# Conn.net
KiCad netlist of a schematic drawn in Altium Designer
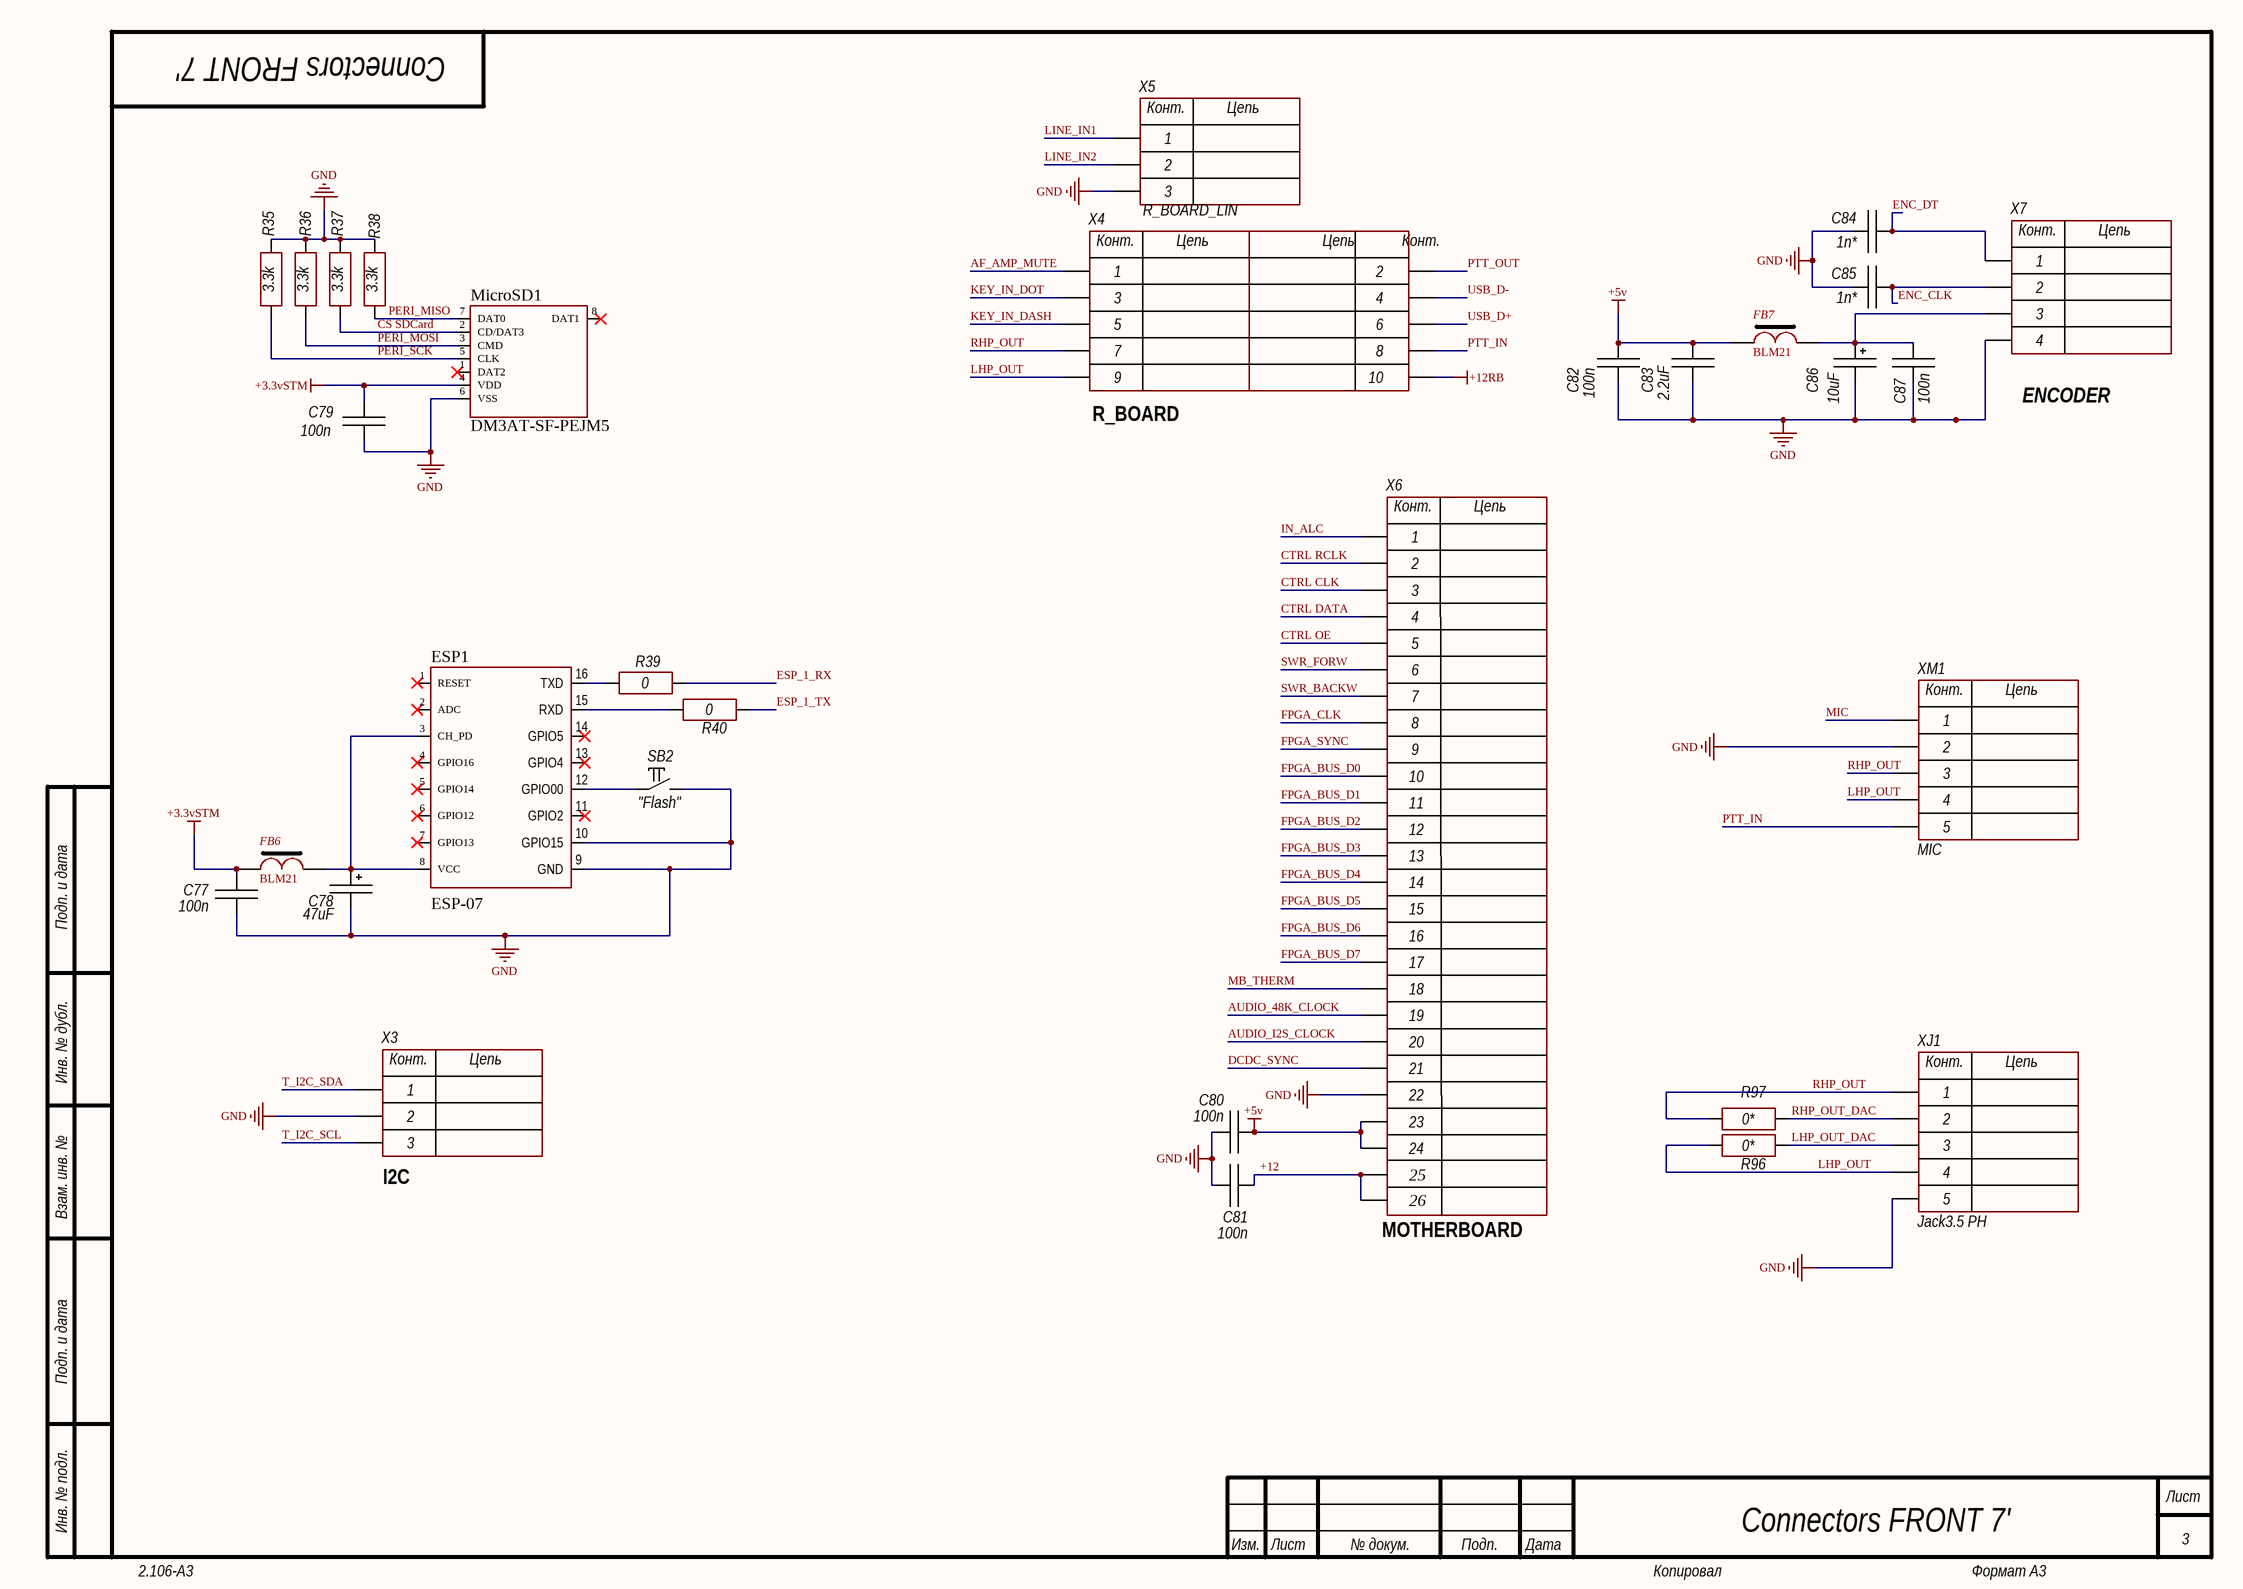
[diagram p0: Conn.SchDoc]

(export (version "E")
  (design (tool "Eeschema 10.0.6"))
  (components
    (comp (ref "C77")
      (value "100n")
      (footprint "standard:CH0805C")
      (libsource (lib "Discrete") (part "Capacitor"))
    )
    (comp (ref "C78")
      (value "47uF")
      (footprint "standard:TANTAL_C")
      (libsource (lib "Discrete") (part "TantalCap"))
    )
    (comp (ref "C79")
      (value "100n")
      (footprint "standard:CH0805C")
      (libsource (lib "Discrete") (part "Capacitor"))
    )
    (comp (ref "C80")
      (value "100n")
      (footprint "standard:CH0805C")
      (libsource (lib "Discrete") (part "Capacitor"))
    )
    (comp (ref "C81")
      (value "100n")
      (footprint "standard:CH0805C")
      (libsource (lib "Discrete") (part "Capacitor"))
    )
    (comp (ref "C82")
      (value "100n")
      (footprint "standard:CH0805C")
      (libsource (lib "Discrete") (part "Capacitor"))
    )
    (comp (ref "C83")
      (value "2.2uF")
      (footprint "standard:CH0805C")
      (libsource (lib "Discrete") (part "Capacitor"))
    )
    (comp (ref "C84")
      (value "1n*")
      (footprint "standard:CH0805C")
      (libsource (lib "Discrete") (part "Capacitor"))
    )
    (comp (ref "C85")
      (value "1n*")
      (footprint "standard:CH0805C")
      (libsource (lib "Discrete") (part "Capacitor"))
    )
    (comp (ref "C86")
      (value "10uF")
      (footprint "standard:TANTAL_B")
      (libsource (lib "Discrete") (part "TantalCap"))
    )
    (comp (ref "C87")
      (value "100n")
      (footprint "standard:CH0805C")
      (libsource (lib "Discrete") (part "Capacitor"))
    )
    (comp (ref "ESP1")
      (value "ESP-07")
      (footprint "ESP8266 ESP-07")
      (libsource (lib "Discrete") (part "ESP-07"))
    )
    (comp (ref "FB6") (value "BLM21") (footprint "CH0805L") (libsource (lib "Discrete") (part "FB-1")))
    (comp (ref "FB7") (value "BLM21") (footprint "CH0805L") (libsource (lib "Discrete") (part "FB-1")))
    (comp (ref "MicroSD1")
      (value "DM3AT-SF-PEJM5")
      (footprint "SD-card")
      (libsource (lib "Discrete") (part "MicroSD"))
    )
    (comp (ref "R35") (value "3.3k") (footprint "standard:CH0805R") (libsource (lib "") (part "Resistor_1")))
    (comp (ref "R36") (value "3.3k") (footprint "standard:CH0805R") (libsource (lib "") (part "Resistor_1")))
    (comp (ref "R37") (value "3.3k") (footprint "standard:CH0805R") (libsource (lib "") (part "Resistor_1")))
    (comp (ref "R38") (value "3.3k") (footprint "standard:CH0805R") (libsource (lib "") (part "Resistor_1")))
    (comp (ref "R39")
      (value "0")
      (footprint "standard:CH0603R")
      (libsource (lib "Discrete") (part "Resistor"))
    )
    (comp (ref "R40")
      (value "0")
      (footprint "standard:CH0603R")
      (libsource (lib "Discrete") (part "Resistor"))
    )
    (comp (ref "R96")
      (value "0*")
      (footprint "standard:CH0603R")
      (libsource (lib "Discrete") (part "Resistor"))
    )
    (comp (ref "R97")
      (value "0*")
      (footprint "standard:CH0603R")
      (libsource (lib "Discrete") (part "Resistor"))
    )
    (comp (ref "SB2")
      (value "\"Flash\"")
      (footprint "custom:BUT: 6x6 SMD")
      (description "6x6 mm")
      (libsource (lib "Connectors") (part "Tactile switches"))
    )
    (comp (ref "X3")
      (value "I2C")
      (footprint "custom:CON: CWF-3")
      (libsource (lib "Connectors") (part "3-Connector"))
    )
    (comp (ref "X4")
      (value "R_BOARD")
      (footprint "custom:CON: BH-10")
      (libsource (lib "Connectors") (part "10(2)-Connector"))
    )
    (comp (ref "X5")
      (value "R_BOARD_LIN")
      (footprint "custom:CON: CWF-3")
      (libsource (lib "Connectors") (part "3-Connector"))
    )
    (comp (ref "X6")
      (value "MOTHERBOARD")
      (footprint "CON: IDC-26")
      (libsource (lib "Connectors") (part "26-Connector"))
    )
    (comp (ref "X7")
      (value "ENCODER")
      (footprint "custom:CON: CWF-4")
      (libsource (lib "Connectors") (part "4-Connector"))
    )
    (comp (ref "XJ1")
      (value "Jack3.5 PH")
      (footprint "custom:CON: PLS-5")
      (libsource (lib "Connectors") (part "5-Connector"))
    )
    (comp (ref "XM1")
      (value "MIC")
      (footprint "custom:CON: PLS-5")
      (libsource (lib "Connectors") (part "5-Connector"))
    )
  )
  (nets
    (net (code "1") (name "+3.3vSTM") (class "Default")
      (node (ref "C77") (pin "2") (pinfunction "2_2") (pintype "power_in"))
      (node (ref "C79") (pin "2") (pinfunction "2_2") (pintype "power_in"))
      (node (ref "FB6") (pin "2") (pinfunction "2_2") (pintype "passive"))
      (node (ref "MicroSD1") (pin "4") (pinfunction "VDD_4") (pintype "passive"))
    )
    (net (code "2") (name "+5v") (class "Default")
      (node (ref "C80") (pin "1") (pinfunction "1_1") (pintype "power_in"))
      (node (ref "C82") (pin "2") (pinfunction "2_2") (pintype "power_in"))
      (node (ref "C83") (pin "2") (pinfunction "2_2") (pintype "power_in"))
      (node (ref "FB7") (pin "2") (pinfunction "2_2") (pintype "passive"))
      (node (ref "X6") (pin "23") (pinfunction "23_23") (pintype "power_in"))
      (node (ref "X6") (pin "24") (pinfunction "24_24") (pintype "power_in"))
    )
    (net (code "3") (name "+12RB") (class "Default")
      (node (ref "X4") (pin "10") (pinfunction "10_10") (pintype "power_in"))
    )
    (net (code "4") (name "/+12") (class "Default")
      (node (ref "C81") (pin "1") (pinfunction "1_1") (pintype "power_in"))
      (node (ref "X6") (pin "25") (pinfunction "25_25") (pintype "power_in"))
      (node (ref "X6") (pin "26") (pinfunction "26_26") (pintype "passive"))
    )
    (net (code "5") (name "/AF_AMP_MUTE") (class "Default")
      (node (ref "X4") (pin "1") (pinfunction "1_1") (pintype "passive"))
    )
    (net (code "6") (name "/AUDIO_48K_CLOCK") (class "Default")
      (node (ref "X6") (pin "19") (pinfunction "19_19") (pintype "power_in"))
    )
    (net (code "7") (name "/AUDIO_I2S_CLOCK") (class "Default")
      (node (ref "X6") (pin "20") (pinfunction "20_20") (pintype "power_in"))
    )
    (net (code "8") (name "/CS SDCard") (class "Default")
      (node (ref "MicroSD1") (pin "2") (pinfunction "CD/DAT3_2") (pintype "passive"))
      (node (ref "R37") (pin "1") (pinfunction "1_1") (pintype "passive"))
    )
    (net (code "9") (name "/CTRL CLK") (class "Default")
      (node (ref "X6") (pin "3") (pinfunction "3_3") (pintype "power_in"))
    )
    (net (code "10") (name "/CTRL DATA") (class "Default")
      (node (ref "X6") (pin "4") (pinfunction "4_4") (pintype "power_in"))
    )
    (net (code "11") (name "/CTRL OE") (class "Default")
      (node (ref "X6") (pin "5") (pinfunction "5_5") (pintype "power_in"))
    )
    (net (code "12") (name "/CTRL RCLK") (class "Default")
      (node (ref "X6") (pin "2") (pinfunction "2_2") (pintype "passive"))
    )
    (net (code "13") (name "/DCDC_SYNC") (class "Default")
      (node (ref "X6") (pin "21") (pinfunction "21_21") (pintype "power_in"))
    )
    (net (code "14") (name "/ENC_CLK") (class "Default")
      (node (ref "C85") (pin "2") (pinfunction "2_2") (pintype "power_in"))
      (node (ref "X7") (pin "2") (pinfunction "2_2") (pintype "passive"))
    )
    (net (code "15") (name "/ENC_DT") (class "Default")
      (node (ref "C84") (pin "2") (pinfunction "2_2") (pintype "power_in"))
      (node (ref "X7") (pin "1") (pinfunction "1_1") (pintype "passive"))
    )
    (net (code "16") (name "/ESP_1_RX") (class "Default")
      (node (ref "R39") (pin "2") (pinfunction "2_2") (pintype "passive"))
    )
    (net (code "17") (name "/ESP_1_TX") (class "Default")
      (node (ref "R40") (pin "2") (pinfunction "2_2") (pintype "passive"))
    )
    (net (code "18") (name "/FPGA_BUS_D0") (class "Default")
      (node (ref "X6") (pin "10") (pinfunction "10_10") (pintype "power_in"))
    )
    (net (code "19") (name "/FPGA_BUS_D1") (class "Default")
      (node (ref "X6") (pin "11") (pinfunction "11_11") (pintype "power_in"))
    )
    (net (code "20") (name "/FPGA_BUS_D2") (class "Default")
      (node (ref "X6") (pin "12") (pinfunction "12_12") (pintype "power_in"))
    )
    (net (code "21") (name "/FPGA_BUS_D3") (class "Default")
      (node (ref "X6") (pin "13") (pinfunction "13_13") (pintype "power_in"))
    )
    (net (code "22") (name "/FPGA_BUS_D4") (class "Default")
      (node (ref "X6") (pin "14") (pinfunction "14_14") (pintype "power_in"))
    )
    (net (code "23") (name "/FPGA_BUS_D5") (class "Default")
      (node (ref "X6") (pin "15") (pinfunction "15_15") (pintype "power_in"))
    )
    (net (code "24") (name "/FPGA_BUS_D6") (class "Default")
      (node (ref "X6") (pin "16") (pinfunction "16_16") (pintype "power_in"))
    )
    (net (code "25") (name "/FPGA_BUS_D7") (class "Default")
      (node (ref "X6") (pin "17") (pinfunction "17_17") (pintype "power_in"))
    )
    (net (code "26") (name "/FPGA_CLK") (class "Default")
      (node (ref "X6") (pin "8") (pinfunction "8_8") (pintype "power_in"))
    )
    (net (code "27") (name "/FPGA_SYNC") (class "Default")
      (node (ref "X6") (pin "9") (pinfunction "9_9") (pintype "power_in"))
    )
    (net (code "28") (name "/IN_ALC") (class "Default")
      (node (ref "X6") (pin "1") (pinfunction "1_1") (pintype "passive"))
    )
    (net (code "29") (name "/KEY_IN_DASH") (class "Default")
      (node (ref "X4") (pin "5") (pinfunction "5_5") (pintype "power_in"))
    )
    (net (code "30") (name "/KEY_IN_DOT") (class "Default")
      (node (ref "X4") (pin "3") (pinfunction "3_3") (pintype "passive"))
    )
    (net (code "31") (name "/LHP_OUT") (class "Default")
      (node (ref "R96") (pin "1") (pinfunction "1_1") (pintype "passive"))
      (node (ref "X4") (pin "9") (pinfunction "9_9") (pintype "power_in"))
      (node (ref "XJ1") (pin "4") (pinfunction "4_4") (pintype "power_in"))
      (node (ref "XM1") (pin "4") (pinfunction "4_4") (pintype "power_in"))
    )
    (net (code "32") (name "/LHP_OUT_DAC") (class "Default")
      (node (ref "R96") (pin "2") (pinfunction "2_2") (pintype "passive"))
      (node (ref "XJ1") (pin "3") (pinfunction "3_3") (pintype "power_in"))
    )
    (net (code "33") (name "/LINE_IN1") (class "Default")
      (node (ref "X5") (pin "1") (pinfunction "1_1") (pintype "passive"))
    )
    (net (code "34") (name "/LINE_IN2") (class "Default")
      (node (ref "X5") (pin "2") (pinfunction "2_2") (pintype "passive"))
    )
    (net (code "35") (name "/MB_THERM") (class "Default")
      (node (ref "X6") (pin "18") (pinfunction "18_18") (pintype "power_in"))
    )
    (net (code "36") (name "/MIC") (class "Default")
      (node (ref "XM1") (pin "1") (pinfunction "1_1") (pintype "passive"))
    )
    (net (code "37") (name "/PERI_MISO") (class "Default")
      (node (ref "MicroSD1") (pin "7") (pinfunction "DAT0_7") (pintype "passive"))
      (node (ref "R38") (pin "1") (pinfunction "1_1") (pintype "passive"))
    )
    (net (code "38") (name "/PERI_MOSI") (class "Default")
      (node (ref "MicroSD1") (pin "3") (pinfunction "CMD_3") (pintype "passive"))
      (node (ref "R36") (pin "1") (pinfunction "1_1") (pintype "passive"))
    )
    (net (code "39") (name "/PERI_SCK") (class "Default")
      (node (ref "MicroSD1") (pin "5") (pinfunction "CLK_5") (pintype "passive"))
      (node (ref "R35") (pin "1") (pinfunction "1_1") (pintype "passive"))
    )
    (net (code "40") (name "/PTT_IN") (class "Default")
      (node (ref "X4") (pin "8") (pinfunction "8_8") (pintype "power_in"))
      (node (ref "XM1") (pin "5") (pinfunction "5_5") (pintype "power_in"))
    )
    (net (code "41") (name "/PTT_OUT") (class "Default")
      (node (ref "X4") (pin "2") (pinfunction "2_2") (pintype "passive"))
    )
    (net (code "42") (name "/RHP_OUT") (class "Default")
      (node (ref "R97") (pin "1") (pinfunction "1_1") (pintype "passive"))
      (node (ref "X4") (pin "7") (pinfunction "7_7") (pintype "power_in"))
      (node (ref "XJ1") (pin "1") (pinfunction "1_1") (pintype "passive"))
      (node (ref "XM1") (pin "3") (pinfunction "3_3") (pintype "power_in"))
    )
    (net (code "43") (name "/RHP_OUT_DAC") (class "Default")
      (node (ref "R97") (pin "2") (pinfunction "2_2") (pintype "passive"))
      (node (ref "XJ1") (pin "2") (pinfunction "2_2") (pintype "passive"))
    )
    (net (code "44") (name "/SWR_BACKW") (class "Default")
      (node (ref "X6") (pin "7") (pinfunction "7_7") (pintype "power_in"))
    )
    (net (code "45") (name "/SWR_FORW") (class "Default")
      (node (ref "X6") (pin "6") (pinfunction "6_6") (pintype "power_in"))
    )
    (net (code "46") (name "/T_I2C_SCL") (class "Default")
      (node (ref "X3") (pin "3") (pinfunction "3_3") (pintype "power_in"))
    )
    (net (code "47") (name "/T_I2C_SDA") (class "Default")
      (node (ref "X3") (pin "1") (pinfunction "1_1") (pintype "passive"))
    )
    (net (code "48") (name "/USB_D+") (class "Default")
      (node (ref "X4") (pin "6") (pinfunction "6_6") (pintype "power_in"))
    )
    (net (code "49") (name "/USB_D-") (class "Default")
      (node (ref "X4") (pin "4") (pinfunction "4_4") (pintype "passive"))
    )
    (net (code "50") (name "GND") (class "Default")
      (node (ref "C77") (pin "1") (pinfunction "1_1") (pintype "power_in"))
      (node (ref "C78") (pin "2") (pinfunction "2_2") (pintype "power_in"))
      (node (ref "C79") (pin "1") (pinfunction "1_1") (pintype "power_in"))
      (node (ref "C80") (pin "2") (pinfunction "2_2") (pintype "power_in"))
      (node (ref "C81") (pin "2") (pinfunction "2_2") (pintype "power_in"))
      (node (ref "C82") (pin "1") (pinfunction "1_1") (pintype "power_in"))
      (node (ref "C83") (pin "1") (pinfunction "1_1") (pintype "power_in"))
      (node (ref "C84") (pin "1") (pinfunction "1_1") (pintype "power_in"))
      (node (ref "C85") (pin "1") (pinfunction "1_1") (pintype "power_in"))
      (node (ref "C86") (pin "2") (pinfunction "2_2") (pintype "power_in"))
      (node (ref "C87") (pin "1") (pinfunction "1_1") (pintype "power_in"))
      (node (ref "ESP1") (pin "10") (pinfunction "GPIO15_10") (pintype "passive"))
      (node (ref "ESP1") (pin "9") (pinfunction "GND_9") (pintype "passive"))
      (node (ref "MicroSD1") (pin "6") (pinfunction "VSS_6") (pintype "passive"))
      (node (ref "R35") (pin "2") (pinfunction "2_2") (pintype "passive"))
      (node (ref "R36") (pin "2") (pinfunction "2_2") (pintype "passive"))
      (node (ref "R37") (pin "2") (pinfunction "2_2") (pintype "passive"))
      (node (ref "R38") (pin "2") (pinfunction "2_2") (pintype "passive"))
      (node (ref "SB2") (pin "2") (pinfunction "2_2") (pintype "passive"))
      (node (ref "X3") (pin "2") (pinfunction "2_2") (pintype "passive"))
      (node (ref "X5") (pin "3") (pinfunction "3_3") (pintype "power_in"))
      (node (ref "X6") (pin "22") (pinfunction "22_22") (pintype "power_in"))
      (node (ref "X7") (pin "4") (pinfunction "4_4") (pintype "power_in"))
      (node (ref "XJ1") (pin "5") (pinfunction "5_5") (pintype "power_in"))
      (node (ref "XM1") (pin "2") (pinfunction "2_2") (pintype "passive"))
    )
    (net (code "51") (name "Net-(C86-Pad1)") (class "Default")
      (node (ref "C86") (pin "1") (pinfunction "1_1") (pintype "power_in"))
      (node (ref "C87") (pin "2") (pinfunction "2_2") (pintype "power_in"))
      (node (ref "FB7") (pin "1") (pinfunction "1_1") (pintype "passive"))
      (node (ref "X7") (pin "3") (pinfunction "3_3") (pintype "power_in"))
    )
    (net (code "52") (name "Net-(ESP1-CH_PD)") (class "Default")
      (node (ref "C78") (pin "1") (pinfunction "1_1") (pintype "power_in"))
      (node (ref "ESP1") (pin "3") (pinfunction "CH_PD_3") (pintype "passive"))
      (node (ref "ESP1") (pin "8") (pinfunction "VCC_8") (pintype "passive"))
      (node (ref "FB6") (pin "1") (pinfunction "1_1") (pintype "passive"))
    )
    (net (code "53") (name "Net-(ESP1-GPIO00)") (class "Default")
      (node (ref "ESP1") (pin "12") (pinfunction "GPIO00_12") (pintype "passive"))
      (node (ref "SB2") (pin "1") (pinfunction "1_1") (pintype "passive"))
    )
    (net (code "54") (name "Net-(ESP1-RXD)") (class "Default")
      (node (ref "ESP1") (pin "15") (pinfunction "RXD_15") (pintype "passive"))
      (node (ref "R40") (pin "1") (pinfunction "1_1") (pintype "passive"))
    )
    (net (code "55") (name "Net-(ESP1-TXD)") (class "Default")
      (node (ref "ESP1") (pin "16") (pinfunction "TXD_16") (pintype "passive"))
      (node (ref "R39") (pin "1") (pinfunction "1_1") (pintype "passive"))
    )
    (net (code "56") (name "unconnected-(ESP1-ADC-Pad2)") (class "Default")
      (node (ref "ESP1") (pin "2") (pinfunction "ADC_2") (pintype "passive+no_connect"))
    )
    (net (code "57") (name "unconnected-(ESP1-GPIO2-Pad11)") (class "Default")
      (node (ref "ESP1") (pin "11") (pinfunction "GPIO2_11") (pintype "passive+no_connect"))
    )
    (net (code "58") (name "unconnected-(ESP1-GPIO4-Pad13)") (class "Default")
      (node (ref "ESP1") (pin "13") (pinfunction "GPIO4_13") (pintype "passive+no_connect"))
    )
    (net (code "59") (name "unconnected-(ESP1-GPIO5-Pad14)") (class "Default")
      (node (ref "ESP1") (pin "14") (pinfunction "GPIO5_14") (pintype "passive+no_connect"))
    )
    (net (code "60") (name "unconnected-(ESP1-GPIO12-Pad6)") (class "Default")
      (node (ref "ESP1") (pin "6") (pinfunction "GPIO12_6") (pintype "passive+no_connect"))
    )
    (net (code "61") (name "unconnected-(ESP1-GPIO13-Pad7)") (class "Default")
      (node (ref "ESP1") (pin "7") (pinfunction "GPIO13_7") (pintype "passive+no_connect"))
    )
    (net (code "62") (name "unconnected-(ESP1-GPIO14-Pad5)") (class "Default")
      (node (ref "ESP1") (pin "5") (pinfunction "GPIO14_5") (pintype "passive+no_connect"))
    )
    (net (code "63") (name "unconnected-(ESP1-GPIO16-Pad4)") (class "Default")
      (node (ref "ESP1") (pin "4") (pinfunction "GPIO16_4") (pintype "passive+no_connect"))
    )
    (net (code "64") (name "unconnected-(ESP1-RESET-Pad1)") (class "Default")
      (node (ref "ESP1") (pin "1") (pinfunction "RESET_1") (pintype "passive+no_connect"))
    )
    (net (code "65") (name "unconnected-(MicroSD1-DAT1-Pad8)") (class "Default")
      (node (ref "MicroSD1") (pin "8") (pinfunction "DAT1_8") (pintype "passive+no_connect"))
    )
    (net (code "66") (name "unconnected-(MicroSD1-DAT2-Pad1)") (class "Default")
      (node (ref "MicroSD1") (pin "1") (pinfunction "DAT2_1") (pintype "passive+no_connect"))
    )
  )
)
